# InterfaceTVSBoardRevB.net
KiCad netlist of a schematic drawn in EAGLE
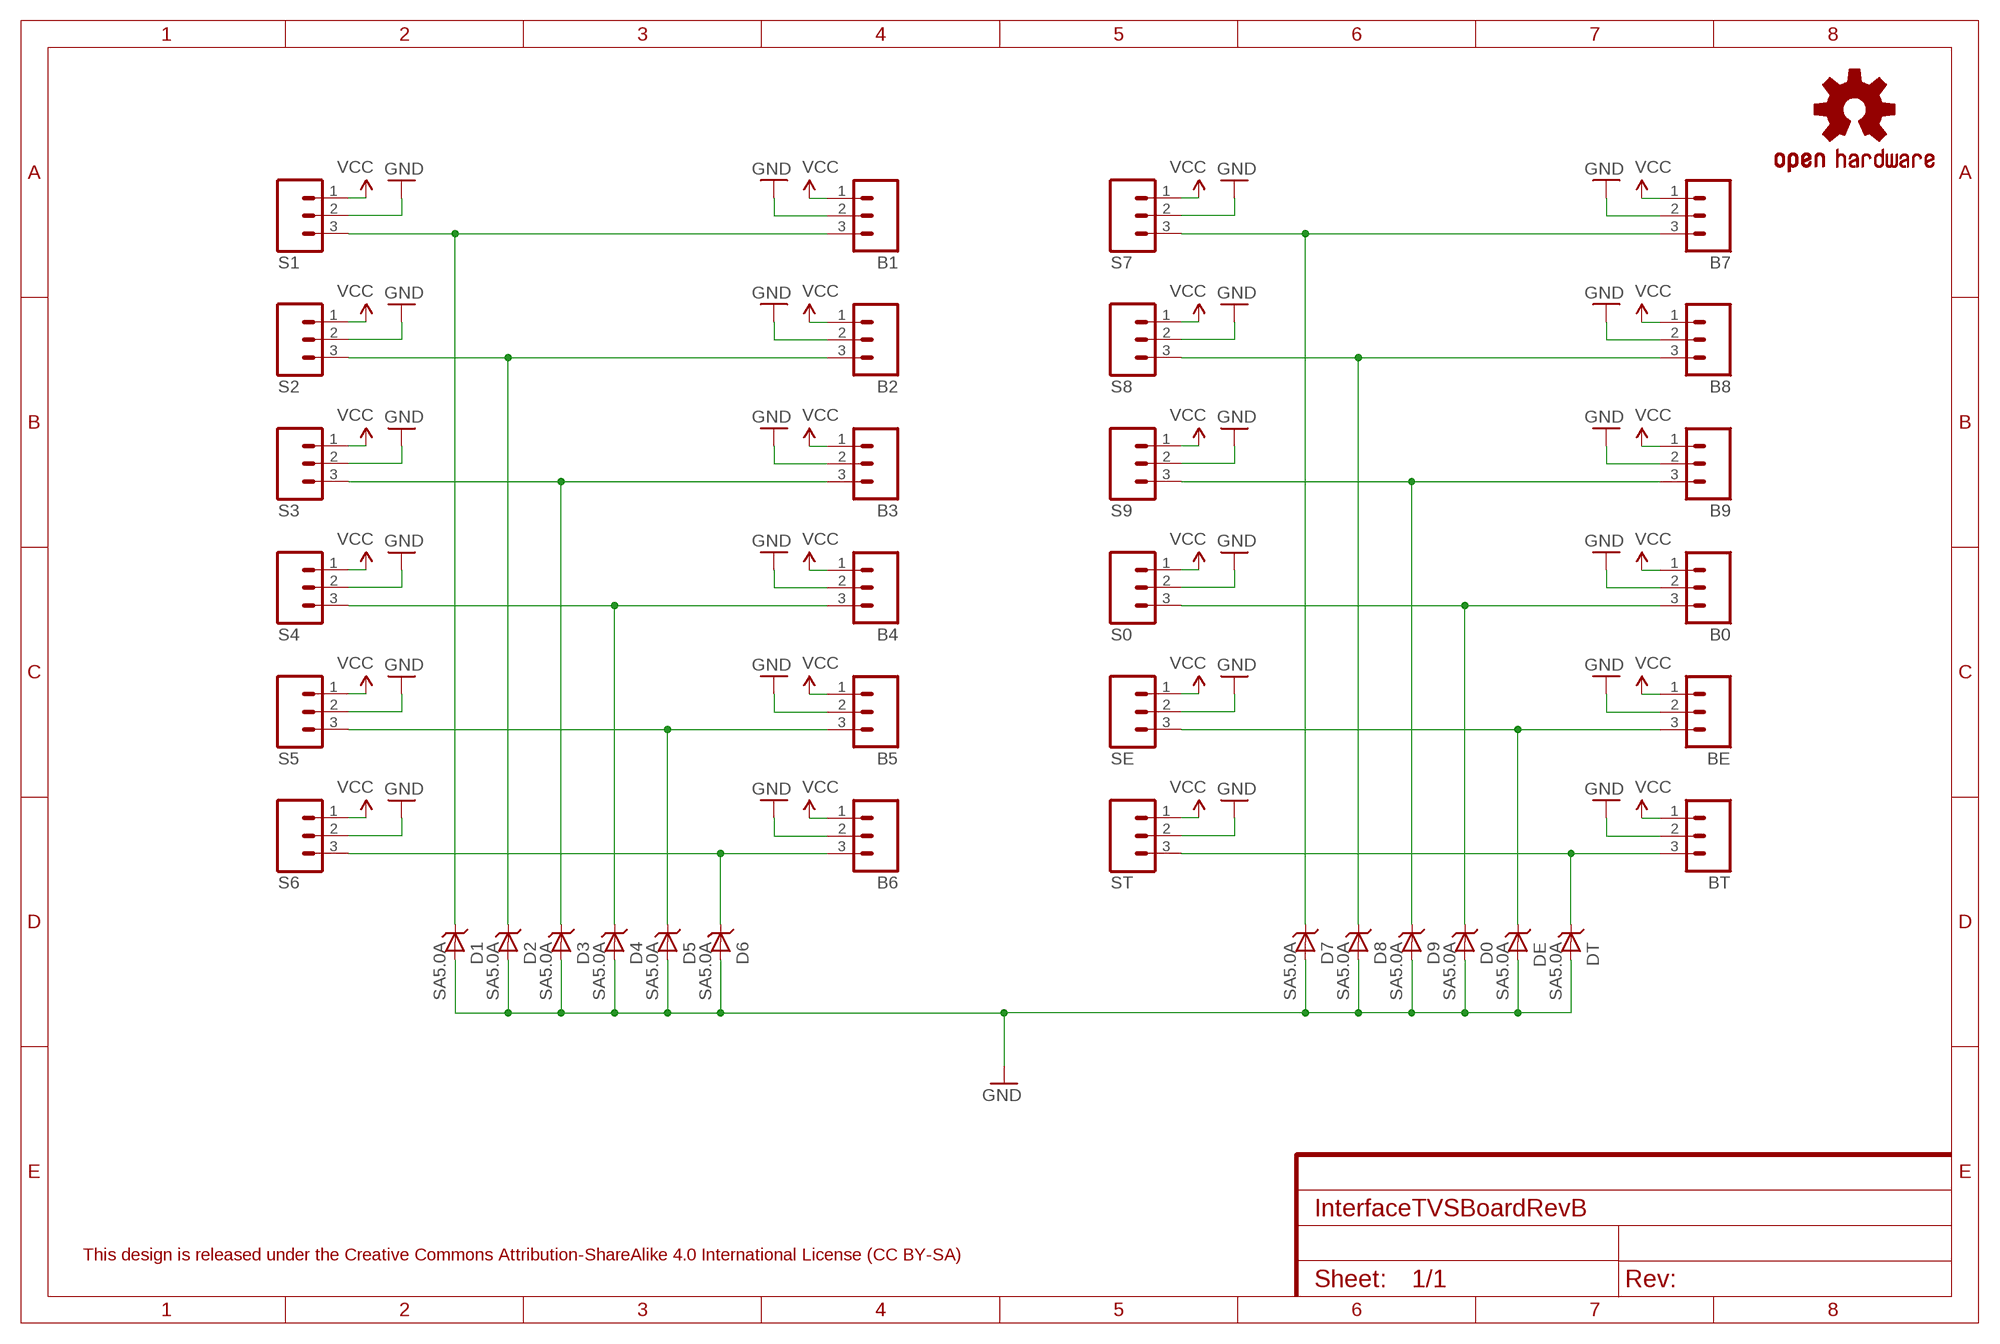
[diagram p0: schematic, sheet 1]

(export (version "E")
  (design (tool "Eeschema 10.0.6"))
  (components
    (comp (ref "B0")
      (value "M03PTH")
      (footprint "eagle-import:1X03")
      (libsource (lib "eagle-import") (part "M03PTH"))
    )
    (comp (ref "B1")
      (value "M03PTH")
      (footprint "eagle-import:1X03")
      (libsource (lib "eagle-import") (part "M03PTH"))
    )
    (comp (ref "B2")
      (value "M03PTH")
      (footprint "eagle-import:1X03")
      (libsource (lib "eagle-import") (part "M03PTH"))
    )
    (comp (ref "B3")
      (value "M03PTH")
      (footprint "eagle-import:1X03")
      (libsource (lib "eagle-import") (part "M03PTH"))
    )
    (comp (ref "B4")
      (value "M03PTH")
      (footprint "eagle-import:1X03")
      (libsource (lib "eagle-import") (part "M03PTH"))
    )
    (comp (ref "B5")
      (value "M03PTH")
      (footprint "eagle-import:1X03")
      (libsource (lib "eagle-import") (part "M03PTH"))
    )
    (comp (ref "B6")
      (value "M03PTH")
      (footprint "eagle-import:1X03")
      (libsource (lib "eagle-import") (part "M03PTH"))
    )
    (comp (ref "B7")
      (value "M03PTH")
      (footprint "eagle-import:1X03")
      (libsource (lib "eagle-import") (part "M03PTH"))
    )
    (comp (ref "B8")
      (value "M03PTH")
      (footprint "eagle-import:1X03")
      (libsource (lib "eagle-import") (part "M03PTH"))
    )
    (comp (ref "B9")
      (value "M03PTH")
      (footprint "eagle-import:1X03")
      (libsource (lib "eagle-import") (part "M03PTH"))
    )
    (comp (ref "BE")
      (value "M03PTH")
      (footprint "eagle-import:1X03")
      (libsource (lib "eagle-import") (part "M03PTH"))
    )
    (comp (ref "BT")
      (value "M03PTH")
      (footprint "eagle-import:1X03")
      (libsource (lib "eagle-import") (part "M03PTH"))
    )
    (comp (ref "D0")
      (value "SA5.0A")
      (footprint "eagle-import:DO41_TVS_UNI")
      (libsource (lib "eagle-import") (part "SA5.0A"))
    )
    (comp (ref "D1")
      (value "SA5.0A")
      (footprint "eagle-import:DO41_TVS_UNI")
      (libsource (lib "eagle-import") (part "SA5.0A"))
    )
    (comp (ref "D2")
      (value "SA5.0A")
      (footprint "eagle-import:DO41_TVS_UNI")
      (libsource (lib "eagle-import") (part "SA5.0A"))
    )
    (comp (ref "D3")
      (value "SA5.0A")
      (footprint "eagle-import:DO41_TVS_UNI")
      (libsource (lib "eagle-import") (part "SA5.0A"))
    )
    (comp (ref "D4")
      (value "SA5.0A")
      (footprint "eagle-import:DO41_TVS_UNI")
      (libsource (lib "eagle-import") (part "SA5.0A"))
    )
    (comp (ref "D5")
      (value "SA5.0A")
      (footprint "eagle-import:DO41_TVS_UNI")
      (libsource (lib "eagle-import") (part "SA5.0A"))
    )
    (comp (ref "D6")
      (value "SA5.0A")
      (footprint "eagle-import:DO41_TVS_UNI")
      (libsource (lib "eagle-import") (part "SA5.0A"))
    )
    (comp (ref "D7")
      (value "SA5.0A")
      (footprint "eagle-import:DO41_TVS_UNI")
      (libsource (lib "eagle-import") (part "SA5.0A"))
    )
    (comp (ref "D8")
      (value "SA5.0A")
      (footprint "eagle-import:DO41_TVS_UNI")
      (libsource (lib "eagle-import") (part "SA5.0A"))
    )
    (comp (ref "D9")
      (value "SA5.0A")
      (footprint "eagle-import:DO41_TVS_UNI")
      (libsource (lib "eagle-import") (part "SA5.0A"))
    )
    (comp (ref "DE")
      (value "SA5.0A")
      (footprint "eagle-import:DO41_TVS_UNI")
      (libsource (lib "eagle-import") (part "SA5.0A"))
    )
    (comp (ref "DT")
      (value "SA5.0A")
      (footprint "eagle-import:DO41_TVS_UNI")
      (libsource (lib "eagle-import") (part "SA5.0A"))
    )
    (comp (ref "LOGO1")
      (value "OSHW-LOGOS")
      (footprint "eagle-import:OSHW-LOGO-S")
      (libsource (lib "eagle-import") (part "OSHW-LOGOS"))
    )
    (comp (ref "S0")
      (value "M03PTH")
      (footprint "eagle-import:1X03")
      (libsource (lib "eagle-import") (part "M03PTH"))
    )
    (comp (ref "S1")
      (value "M03PTH")
      (footprint "eagle-import:1X03")
      (libsource (lib "eagle-import") (part "M03PTH"))
    )
    (comp (ref "S2")
      (value "M03PTH")
      (footprint "eagle-import:1X03")
      (libsource (lib "eagle-import") (part "M03PTH"))
    )
    (comp (ref "S3")
      (value "M03PTH")
      (footprint "eagle-import:1X03")
      (libsource (lib "eagle-import") (part "M03PTH"))
    )
    (comp (ref "S4")
      (value "M03PTH")
      (footprint "eagle-import:1X03")
      (libsource (lib "eagle-import") (part "M03PTH"))
    )
    (comp (ref "S5")
      (value "M03PTH")
      (footprint "eagle-import:1X03")
      (libsource (lib "eagle-import") (part "M03PTH"))
    )
    (comp (ref "S6")
      (value "M03PTH")
      (footprint "eagle-import:1X03")
      (libsource (lib "eagle-import") (part "M03PTH"))
    )
    (comp (ref "S7")
      (value "M03PTH")
      (footprint "eagle-import:1X03")
      (libsource (lib "eagle-import") (part "M03PTH"))
    )
    (comp (ref "S8")
      (value "M03PTH")
      (footprint "eagle-import:1X03")
      (libsource (lib "eagle-import") (part "M03PTH"))
    )
    (comp (ref "S9")
      (value "M03PTH")
      (footprint "eagle-import:1X03")
      (libsource (lib "eagle-import") (part "M03PTH"))
    )
    (comp (ref "SE")
      (value "M03PTH")
      (footprint "eagle-import:1X03")
      (libsource (lib "eagle-import") (part "M03PTH"))
    )
    (comp (ref "ST")
      (value "M03PTH")
      (footprint "eagle-import:1X03")
      (libsource (lib "eagle-import") (part "M03PTH"))
    )
  )
  (nets
    (net (code "1") (name "GND") (class "Default")
      (node (ref "B0") (pin "2") (pinfunction "2_2") (pintype "passive"))
      (node (ref "B1") (pin "2") (pinfunction "2_2") (pintype "passive"))
      (node (ref "B2") (pin "2") (pinfunction "2_2") (pintype "passive"))
      (node (ref "B3") (pin "2") (pinfunction "2_2") (pintype "passive"))
      (node (ref "B4") (pin "2") (pinfunction "2_2") (pintype "passive"))
      (node (ref "B5") (pin "2") (pinfunction "2_2") (pintype "passive"))
      (node (ref "B6") (pin "2") (pinfunction "2_2") (pintype "passive"))
      (node (ref "B7") (pin "2") (pinfunction "2_2") (pintype "passive"))
      (node (ref "B8") (pin "2") (pinfunction "2_2") (pintype "passive"))
      (node (ref "B9") (pin "2") (pinfunction "2_2") (pintype "passive"))
      (node (ref "BE") (pin "2") (pinfunction "2_2") (pintype "passive"))
      (node (ref "BT") (pin "2") (pinfunction "2_2") (pintype "passive"))
      (node (ref "D0") (pin "ANODE") (pinfunction "ANODE_ANODE") (pintype "passive"))
      (node (ref "D1") (pin "ANODE") (pinfunction "ANODE_ANODE") (pintype "passive"))
      (node (ref "D2") (pin "ANODE") (pinfunction "ANODE_ANODE") (pintype "passive"))
      (node (ref "D3") (pin "ANODE") (pinfunction "ANODE_ANODE") (pintype "passive"))
      (node (ref "D4") (pin "ANODE") (pinfunction "ANODE_ANODE") (pintype "passive"))
      (node (ref "D5") (pin "ANODE") (pinfunction "ANODE_ANODE") (pintype "passive"))
      (node (ref "D6") (pin "ANODE") (pinfunction "ANODE_ANODE") (pintype "passive"))
      (node (ref "D7") (pin "ANODE") (pinfunction "ANODE_ANODE") (pintype "passive"))
      (node (ref "D8") (pin "ANODE") (pinfunction "ANODE_ANODE") (pintype "passive"))
      (node (ref "D9") (pin "ANODE") (pinfunction "ANODE_ANODE") (pintype "passive"))
      (node (ref "DE") (pin "ANODE") (pinfunction "ANODE_ANODE") (pintype "passive"))
      (node (ref "DT") (pin "ANODE") (pinfunction "ANODE_ANODE") (pintype "passive"))
      (node (ref "S0") (pin "2") (pinfunction "2_2") (pintype "passive"))
      (node (ref "S1") (pin "2") (pinfunction "2_2") (pintype "passive"))
      (node (ref "S2") (pin "2") (pinfunction "2_2") (pintype "passive"))
      (node (ref "S3") (pin "2") (pinfunction "2_2") (pintype "passive"))
      (node (ref "S4") (pin "2") (pinfunction "2_2") (pintype "passive"))
      (node (ref "S5") (pin "2") (pinfunction "2_2") (pintype "passive"))
      (node (ref "S6") (pin "2") (pinfunction "2_2") (pintype "passive"))
      (node (ref "S7") (pin "2") (pinfunction "2_2") (pintype "passive"))
      (node (ref "S8") (pin "2") (pinfunction "2_2") (pintype "passive"))
      (node (ref "S9") (pin "2") (pinfunction "2_2") (pintype "passive"))
      (node (ref "SE") (pin "2") (pinfunction "2_2") (pintype "passive"))
      (node (ref "ST") (pin "2") (pinfunction "2_2") (pintype "passive"))
    )
    (net (code "2") (name "Net-(B0-Pad3)") (class "Default")
      (node (ref "B0") (pin "3") (pinfunction "3_3") (pintype "passive"))
      (node (ref "D0") (pin "CATHODE") (pinfunction "CATHODE_CATHODE") (pintype "passive"))
      (node (ref "S0") (pin "3") (pinfunction "3_3") (pintype "passive"))
    )
    (net (code "3") (name "Net-(B1-Pad3)") (class "Default")
      (node (ref "B1") (pin "3") (pinfunction "3_3") (pintype "passive"))
      (node (ref "D1") (pin "CATHODE") (pinfunction "CATHODE_CATHODE") (pintype "passive"))
      (node (ref "S1") (pin "3") (pinfunction "3_3") (pintype "passive"))
    )
    (net (code "4") (name "Net-(B2-Pad3)") (class "Default")
      (node (ref "B2") (pin "3") (pinfunction "3_3") (pintype "passive"))
      (node (ref "D2") (pin "CATHODE") (pinfunction "CATHODE_CATHODE") (pintype "passive"))
      (node (ref "S2") (pin "3") (pinfunction "3_3") (pintype "passive"))
    )
    (net (code "5") (name "Net-(B3-Pad3)") (class "Default")
      (node (ref "B3") (pin "3") (pinfunction "3_3") (pintype "passive"))
      (node (ref "D3") (pin "CATHODE") (pinfunction "CATHODE_CATHODE") (pintype "passive"))
      (node (ref "S3") (pin "3") (pinfunction "3_3") (pintype "passive"))
    )
    (net (code "6") (name "Net-(B4-Pad3)") (class "Default")
      (node (ref "B4") (pin "3") (pinfunction "3_3") (pintype "passive"))
      (node (ref "D4") (pin "CATHODE") (pinfunction "CATHODE_CATHODE") (pintype "passive"))
      (node (ref "S4") (pin "3") (pinfunction "3_3") (pintype "passive"))
    )
    (net (code "7") (name "Net-(B5-Pad3)") (class "Default")
      (node (ref "B5") (pin "3") (pinfunction "3_3") (pintype "passive"))
      (node (ref "D5") (pin "CATHODE") (pinfunction "CATHODE_CATHODE") (pintype "passive"))
      (node (ref "S5") (pin "3") (pinfunction "3_3") (pintype "passive"))
    )
    (net (code "8") (name "Net-(B6-Pad3)") (class "Default")
      (node (ref "B6") (pin "3") (pinfunction "3_3") (pintype "passive"))
      (node (ref "D6") (pin "CATHODE") (pinfunction "CATHODE_CATHODE") (pintype "passive"))
      (node (ref "S6") (pin "3") (pinfunction "3_3") (pintype "passive"))
    )
    (net (code "9") (name "Net-(B7-Pad3)") (class "Default")
      (node (ref "B7") (pin "3") (pinfunction "3_3") (pintype "passive"))
      (node (ref "D7") (pin "CATHODE") (pinfunction "CATHODE_CATHODE") (pintype "passive"))
      (node (ref "S7") (pin "3") (pinfunction "3_3") (pintype "passive"))
    )
    (net (code "10") (name "Net-(B8-Pad3)") (class "Default")
      (node (ref "B8") (pin "3") (pinfunction "3_3") (pintype "passive"))
      (node (ref "D8") (pin "CATHODE") (pinfunction "CATHODE_CATHODE") (pintype "passive"))
      (node (ref "S8") (pin "3") (pinfunction "3_3") (pintype "passive"))
    )
    (net (code "11") (name "Net-(B9-Pad3)") (class "Default")
      (node (ref "B9") (pin "3") (pinfunction "3_3") (pintype "passive"))
      (node (ref "D9") (pin "CATHODE") (pinfunction "CATHODE_CATHODE") (pintype "passive"))
      (node (ref "S9") (pin "3") (pinfunction "3_3") (pintype "passive"))
    )
    (net (code "12") (name "Net-(BE-Pad3)") (class "Default")
      (node (ref "BE") (pin "3") (pinfunction "3_3") (pintype "passive"))
      (node (ref "DE") (pin "CATHODE") (pinfunction "CATHODE_CATHODE") (pintype "passive"))
      (node (ref "SE") (pin "3") (pinfunction "3_3") (pintype "passive"))
    )
    (net (code "13") (name "Net-(BT-Pad3)") (class "Default")
      (node (ref "BT") (pin "3") (pinfunction "3_3") (pintype "passive"))
      (node (ref "DT") (pin "CATHODE") (pinfunction "CATHODE_CATHODE") (pintype "passive"))
      (node (ref "ST") (pin "3") (pinfunction "3_3") (pintype "passive"))
    )
    (net (code "14") (name "VCC") (class "Default")
      (node (ref "B0") (pin "1") (pinfunction "1_1") (pintype "passive"))
      (node (ref "B1") (pin "1") (pinfunction "1_1") (pintype "passive"))
      (node (ref "B2") (pin "1") (pinfunction "1_1") (pintype "passive"))
      (node (ref "B3") (pin "1") (pinfunction "1_1") (pintype "passive"))
      (node (ref "B4") (pin "1") (pinfunction "1_1") (pintype "passive"))
      (node (ref "B5") (pin "1") (pinfunction "1_1") (pintype "passive"))
      (node (ref "B6") (pin "1") (pinfunction "1_1") (pintype "passive"))
      (node (ref "B7") (pin "1") (pinfunction "1_1") (pintype "passive"))
      (node (ref "B8") (pin "1") (pinfunction "1_1") (pintype "passive"))
      (node (ref "B9") (pin "1") (pinfunction "1_1") (pintype "passive"))
      (node (ref "BE") (pin "1") (pinfunction "1_1") (pintype "passive"))
      (node (ref "BT") (pin "1") (pinfunction "1_1") (pintype "passive"))
      (node (ref "S0") (pin "1") (pinfunction "1_1") (pintype "passive"))
      (node (ref "S1") (pin "1") (pinfunction "1_1") (pintype "passive"))
      (node (ref "S2") (pin "1") (pinfunction "1_1") (pintype "passive"))
      (node (ref "S3") (pin "1") (pinfunction "1_1") (pintype "passive"))
      (node (ref "S4") (pin "1") (pinfunction "1_1") (pintype "passive"))
      (node (ref "S5") (pin "1") (pinfunction "1_1") (pintype "passive"))
      (node (ref "S6") (pin "1") (pinfunction "1_1") (pintype "passive"))
      (node (ref "S7") (pin "1") (pinfunction "1_1") (pintype "passive"))
      (node (ref "S8") (pin "1") (pinfunction "1_1") (pintype "passive"))
      (node (ref "S9") (pin "1") (pinfunction "1_1") (pintype "passive"))
      (node (ref "SE") (pin "1") (pinfunction "1_1") (pintype "passive"))
      (node (ref "ST") (pin "1") (pinfunction "1_1") (pintype "passive"))
    )
  )
)
